# blink1mk3-prog-jig1.net
KiCad netlist of a schematic drawn in EAGLE
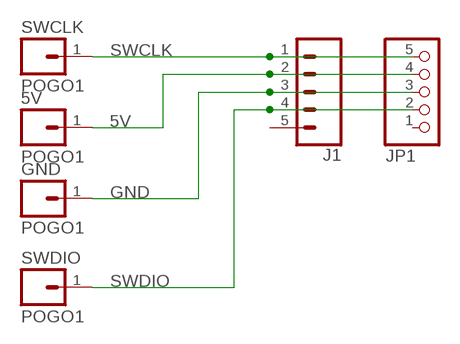
[diagram p0: schematic, sheet 1]

(export (version "E")
  (design (tool "Eeschema 10.0.6"))
  (components
    (comp (ref "5V")
      (value "POGO1")
      (footprint "eagle-import:MILLMAX-0928-POGO-THRU")
      (libsource (lib "eagle-import") (part "POGO1"))
    )
    (comp (ref "GND")
      (value "POGO1")
      (footprint "eagle-import:MILLMAX-0928-POGO-THRU")
      (libsource (lib "eagle-import") (part "POGO1"))
    )
    (comp (ref "J1")
      (value "CONN_05")
      (footprint "eagle-import:1X05")
      (libsource (lib "eagle-import") (part "CONN_05"))
    )
    (comp (ref "JP1")
      (value "PINHD-1X5/90")
      (footprint "eagle-import:1X05_90")
      (libsource (lib "eagle-import") (part "PINHD-1X5/90"))
    )
    (comp (ref "SWCLK")
      (value "POGO1")
      (footprint "eagle-import:MILLMAX-0928-POGO-THRU")
      (libsource (lib "eagle-import") (part "POGO1"))
    )
    (comp (ref "SWDIO")
      (value "POGO1")
      (footprint "eagle-import:MILLMAX-0928-POGO-THRU")
      (libsource (lib "eagle-import") (part "POGO1"))
    )
  )
  (nets
    (net (code "1") (name "/5V") (class "Default")
      (node (ref "5V") (pin "1") (pinfunction "1_1") (pintype "passive"))
      (node (ref "J1") (pin "2") (pinfunction "2_2") (pintype "passive"))
      (node (ref "JP1") (pin "4") (pinfunction "4_4") (pintype "passive"))
    )
    (net (code "2") (name "/GND") (class "Default")
      (node (ref "GND") (pin "1") (pinfunction "1_1") (pintype "passive"))
      (node (ref "J1") (pin "3") (pinfunction "3_3") (pintype "passive"))
      (node (ref "JP1") (pin "3") (pinfunction "3_3") (pintype "passive"))
    )
    (net (code "3") (name "/SWCLK") (class "Default")
      (node (ref "J1") (pin "1") (pinfunction "1_1") (pintype "passive"))
      (node (ref "JP1") (pin "5") (pinfunction "5_5") (pintype "passive"))
      (node (ref "SWCLK") (pin "1") (pinfunction "1_1") (pintype "passive"))
    )
    (net (code "4") (name "/SWDIO") (class "Default")
      (node (ref "J1") (pin "4") (pinfunction "4_4") (pintype "passive"))
      (node (ref "JP1") (pin "2") (pinfunction "2_2") (pintype "passive"))
      (node (ref "SWDIO") (pin "1") (pinfunction "1_1") (pintype "passive"))
    )
    (net (code "5") (name "unconnected-(J1-Pad5)") (class "Default")
      (node (ref "J1") (pin "5") (pinfunction "5_5") (pintype "passive"))
    )
    (net (code "6") (name "unconnected-(JP1-Pad1)") (class "Default")
      (node (ref "JP1") (pin "1") (pinfunction "1_1") (pintype "passive"))
    )
  )
)
